# IP5306_IP51081.net
KiCad netlist of a schematic drawn in Altium Designer
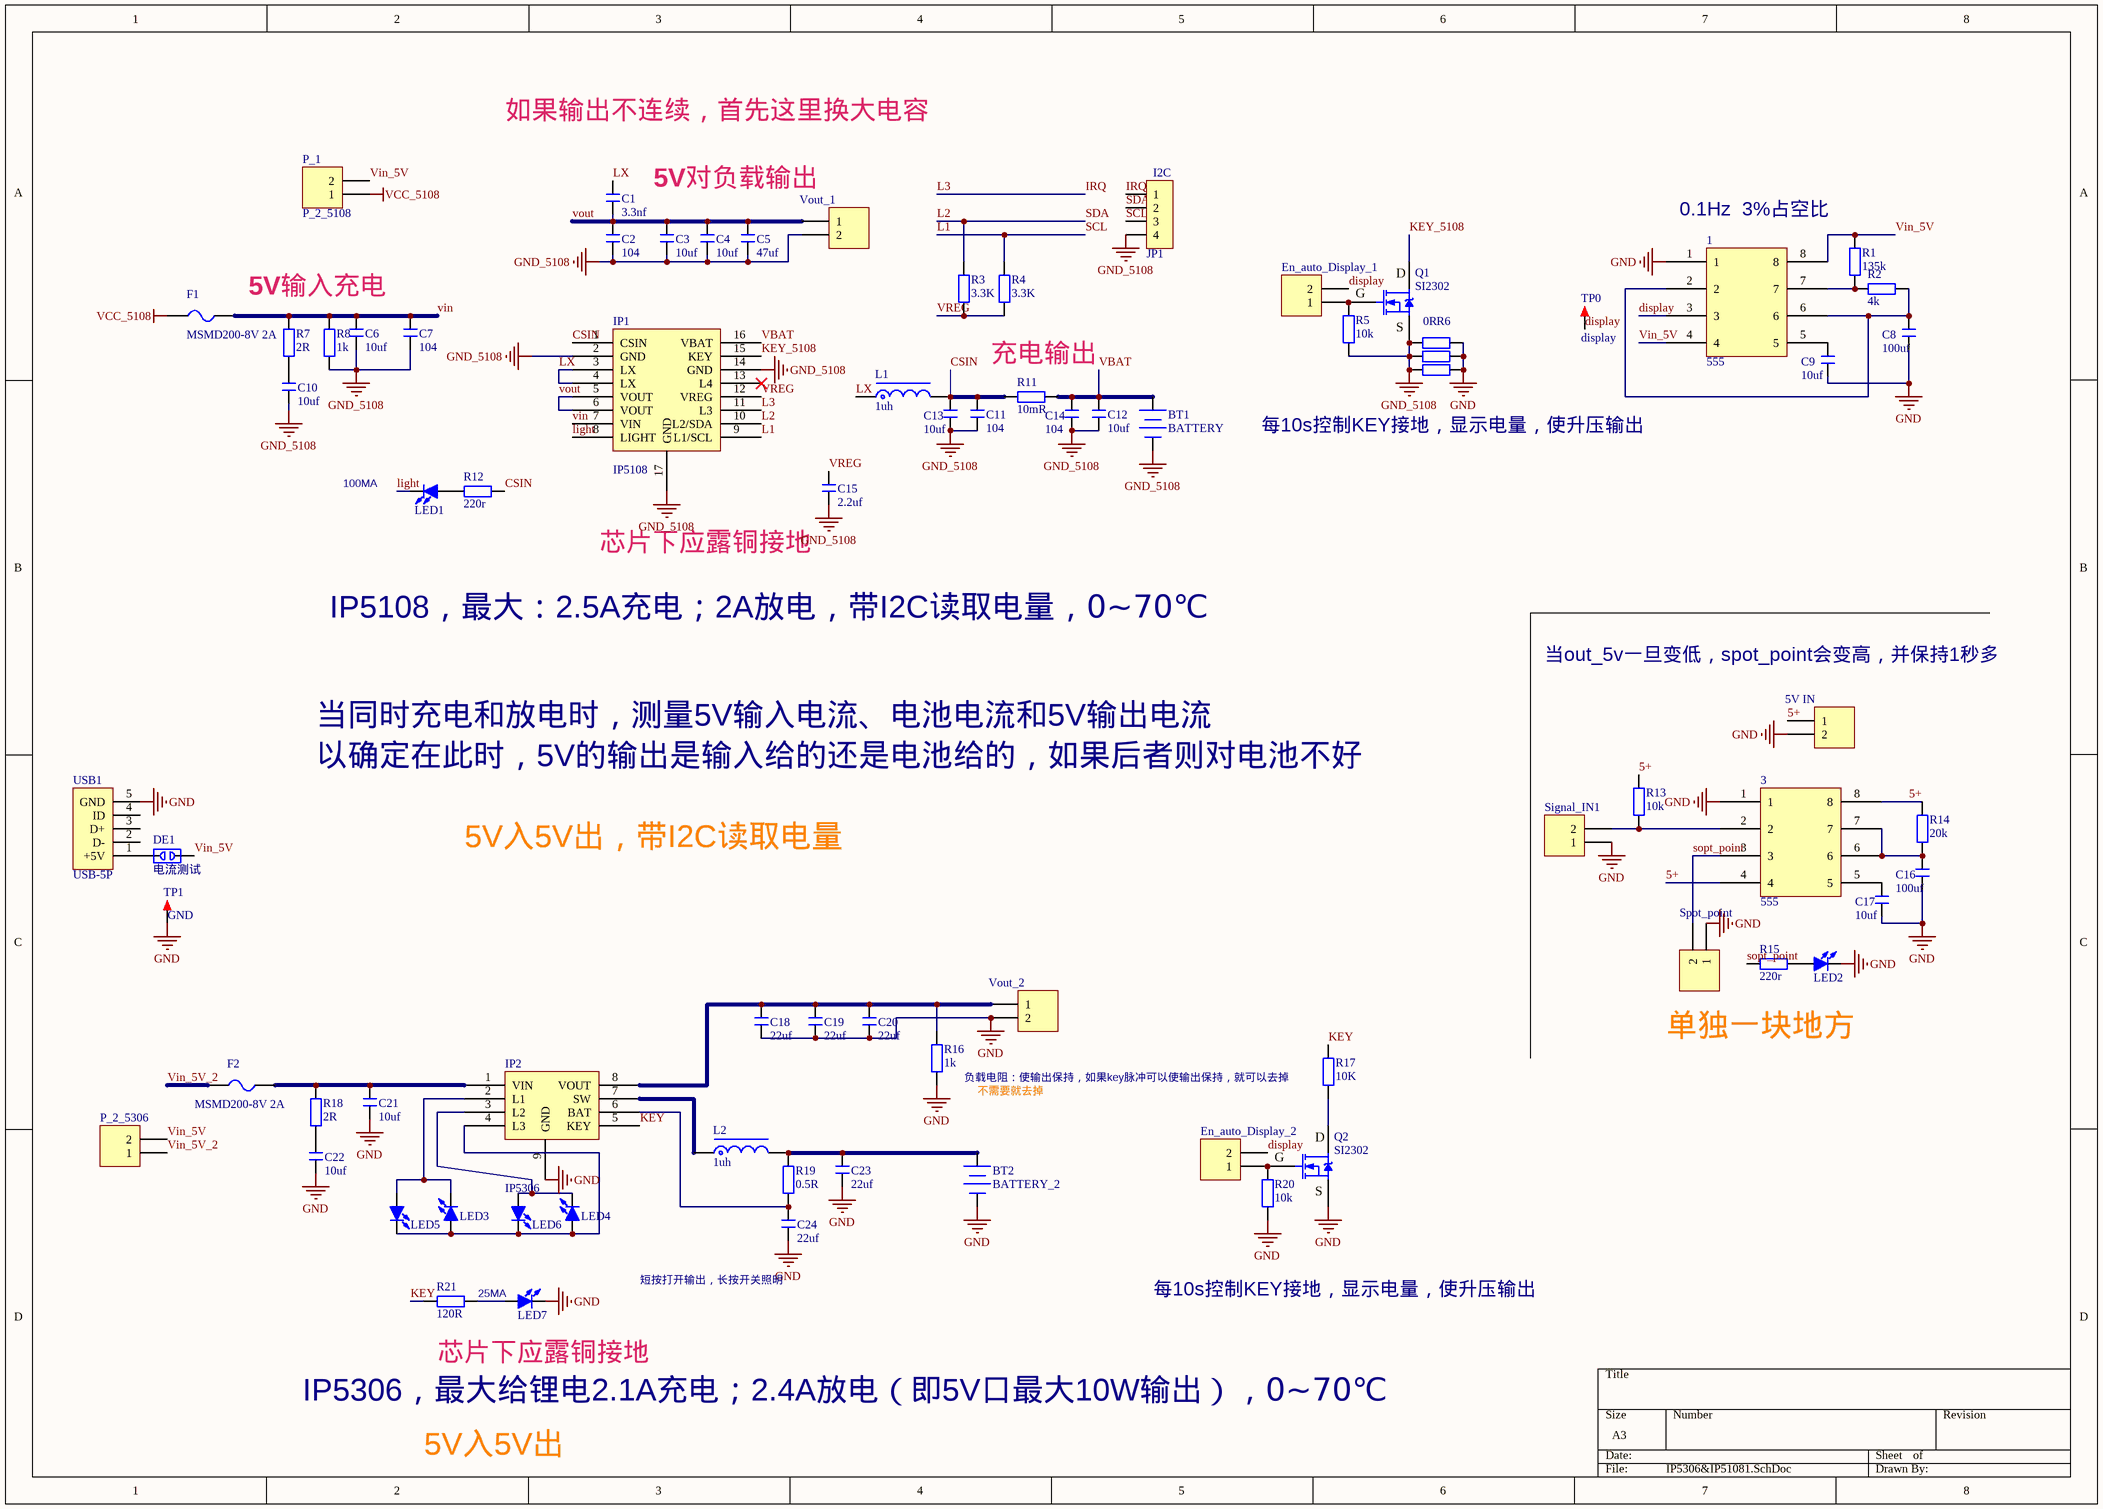
[diagram p0: IP5306&IP51081.SchDoc]

(export (version "E")
  (design (tool "Eeschema 10.0.6"))
  (components
    (comp (ref "1") (value "555") (footprint "SOP8_N") (libsource (lib "集成块") (part "555")))
    (comp (ref "2")
      (value "5V IN")
      (footprint "HDR1X2")
      (description "Header, 2-Pin")
      (fields (field (name "PUBLISHER") "Altium Limited"))
      (libsource (lib "") (part "Header 2_1"))
    )
    (comp (ref "3") (value "555") (footprint "SOP8_N") (libsource (lib "集成块") (part "555")))
    (comp (ref "BT1")
      (value "BATTERY")
      (footprint "BAT-2")
      (description "Multicell Battery")
      (fields (field (name "PUBLISHER") "Altium Limited"))
      (libsource (lib "rest") (part "BATTERY"))
    )
    (comp (ref "BT2")
      (value "BATTERY_2")
      (footprint "BAT-2")
      (description "Multicell Battery")
      (fields (field (name "PUBLISHER") "Altium Limited"))
      (libsource (lib "rest") (part "BATTERY"))
    )
    (comp (ref "C1")
      (value "3.3nf")
      (footprint "C 0805_M")
      (description "无极性贴片电容")
      (libsource (lib "3.1   - 电阻-电容-电感") (part "C"))
    )
    (comp (ref "C2")
      (value "104")
      (footprint "C 0805_M")
      (description "无极性贴片电容")
      (libsource (lib "3.1   - 电阻-电容-电感") (part "C"))
    )
    (comp (ref "C3")
      (value "10uf")
      (footprint "C 0805_M")
      (description "无极性贴片电容")
      (libsource (lib "3.1   - 电阻-电容-电感") (part "C"))
    )
    (comp (ref "C4")
      (value "10uf")
      (footprint "C 0805_M")
      (description "无极性贴片电容")
      (libsource (lib "3.1   - 电阻-电容-电感") (part "C"))
    )
    (comp (ref "C5")
      (value "47uf")
      (footprint "CD A(3216)")
      (description "无极性贴片电容")
      (libsource (lib "3.1   - 电阻-电容-电感") (part "C"))
    )
    (comp (ref "C6")
      (value "10uf")
      (footprint "C 0805_M")
      (description "无极性贴片电容")
      (libsource (lib "3.1   - 电阻-电容-电感") (part "C"))
    )
    (comp (ref "C7")
      (value "104")
      (footprint "C 0805_M")
      (description "无极性贴片电容")
      (libsource (lib "3.1   - 电阻-电容-电感") (part "C"))
    )
    (comp (ref "C8")
      (value "100uf")
      (footprint "CD B(3528)")
      (description "无极性贴片电容")
      (libsource (lib "3.1   - 电阻-电容-电感") (part "C"))
    )
    (comp (ref "C9")
      (value "10uf")
      (footprint "C 0805_M")
      (description "无极性贴片电容")
      (libsource (lib "3.1   - 电阻-电容-电感") (part "C"))
    )
    (comp (ref "C10")
      (value "10uf")
      (footprint "C 0805_M")
      (description "无极性贴片电容")
      (libsource (lib "3.1   - 电阻-电容-电感") (part "C"))
    )
    (comp (ref "C11")
      (value "104")
      (footprint "C 0805_M")
      (description "无极性贴片电容")
      (libsource (lib "3.1   - 电阻-电容-电感") (part "C"))
    )
    (comp (ref "C12")
      (value "10uf")
      (footprint "C 0805_M")
      (description "无极性贴片电容")
      (libsource (lib "3.1   - 电阻-电容-电感") (part "C"))
    )
    (comp (ref "C13")
      (value "10uf")
      (footprint "C 0805_M")
      (description "无极性贴片电容")
      (libsource (lib "3.1   - 电阻-电容-电感") (part "C"))
    )
    (comp (ref "C14")
      (value "104")
      (footprint "C 0805_M")
      (description "无极性贴片电容")
      (libsource (lib "3.1   - 电阻-电容-电感") (part "C"))
    )
    (comp (ref "C15")
      (value "2.2uf")
      (footprint "C 0805_M")
      (description "无极性贴片电容")
      (libsource (lib "3.1   - 电阻-电容-电感") (part "C"))
    )
    (comp (ref "C16")
      (value "100uf")
      (footprint "CD B(3528)")
      (description "无极性贴片电容")
      (libsource (lib "3.1   - 电阻-电容-电感") (part "C"))
    )
    (comp (ref "C17")
      (value "10uf")
      (footprint "C 0805_M")
      (description "无极性贴片电容")
      (libsource (lib "3.1   - 电阻-电容-电感") (part "C"))
    )
    (comp (ref "C18")
      (value "22uf")
      (footprint "C 0805_M")
      (description "无极性贴片电容")
      (libsource (lib "3.1   - 电阻-电容-电感") (part "C"))
    )
    (comp (ref "C19")
      (value "22uf")
      (footprint "C 0805_M")
      (description "无极性贴片电容")
      (libsource (lib "3.1   - 电阻-电容-电感") (part "C"))
    )
    (comp (ref "C20")
      (value "22uf")
      (footprint "C 0805_M")
      (description "无极性贴片电容")
      (libsource (lib "3.1   - 电阻-电容-电感") (part "C"))
    )
    (comp (ref "C21")
      (value "10uf")
      (footprint "C 0805_M")
      (description "无极性贴片电容")
      (libsource (lib "3.1   - 电阻-电容-电感") (part "C"))
    )
    (comp (ref "C22")
      (value "10uf")
      (footprint "C 0805_M")
      (description "无极性贴片电容")
      (libsource (lib "3.1   - 电阻-电容-电感") (part "C"))
    )
    (comp (ref "C23")
      (value "22uf")
      (footprint "C 0805_M")
      (description "无极性贴片电容")
      (libsource (lib "3.1   - 电阻-电容-电感") (part "C"))
    )
    (comp (ref "C24")
      (value "22uf")
      (footprint "C 0805_M")
      (description "无极性贴片电容")
      (libsource (lib "3.1   - 电阻-电容-电感") (part "C"))
    )
    (comp (ref "DE1")
      (value "电流测试")
      (footprint "DEBUG_B")
      (description "调试断点焊盘")
      (libsource (lib "15.1 - 未分类器件") (part "DEBUG"))
    )
    (comp (ref "En_auto_Display_1")
      (value "En_auto_Display_1")
      (footprint "HDR1X2")
      (description "Header, 2-Pin")
      (fields (field (name "PUBLISHER") "Altium Limited"))
      (libsource (lib "Miscellaneous Connectors") (part "Header 2"))
    )
    (comp (ref "En_auto_Display_2")
      (value "En_auto_Display_2")
      (footprint "HDR1X2")
      (description "Header, 2-Pin")
      (fields (field (name "PUBLISHER") "Altium Limited"))
      (libsource (lib "Miscellaneous Connectors") (part "Header 2"))
    )
    (comp (ref "F1")
      (value "MSMD200-8V 2A")
      (footprint "FU 1812")
      (description "贴片保险丝")
      (libsource (lib "10.1 - 保险丝-晶振") (part "FU"))
    )
    (comp (ref "F2")
      (value "MSMD200-8V 2A")
      (footprint "FU 1812")
      (description "贴片保险丝")
      (libsource (lib "10.1 - 保险丝-晶振") (part "FU"))
    )
    (comp (ref "IP1") (value "IP5108") (footprint "ESOP16_M") (libsource (lib "电源管理") (part "IP5108")))
    (comp (ref "IP2") (value "IP5306") (footprint "ESOP8_M") (libsource (lib "电源管理") (part "IP5306")))
    (comp (ref "JP1")
      (value "I2C")
      (footprint "HDR2.54-LI-4P")
      (description "4P接插件")
      (libsource (lib "4.5   - 接插件-脚距2.54") (part "Header 4"))
    )
    (comp (ref "L1")
      (value "1uh")
      (footprint "L-SMD-0630")
      (description "功率屏蔽电感")
      (libsource (lib "3.1   - 电阻-电容-电感") (part "L-CDRH"))
    )
    (comp (ref "L2")
      (value "1uh")
      (footprint "L-SMD-0630")
      (description "功率屏蔽电感")
      (libsource (lib "3.1   - 电阻-电容-电感") (part "L-CDRH"))
    )
    (comp (ref "LED1")
      (value "light")
      (footprint "LED 0805G")
      (description "贴片LED")
      (libsource (lib "9.1   - LED") (part "LED-SMD"))
    )
    (comp (ref "LED2")
      (value "led")
      (footprint "LED 0805G")
      (description "贴片LED")
      (libsource (lib "9.1   - LED") (part "LED-SMD"))
    )
    (comp (ref "LED3")
      (value "led2")
      (footprint "LED 0805G")
      (description "贴片LED")
      (libsource (lib "9.1   - LED") (part "LED-SMD"))
    )
    (comp (ref "LED4")
      (value "led4")
      (footprint "LED 0805G")
      (description "贴片LED")
      (libsource (lib "9.1   - LED") (part "LED-SMD"))
    )
    (comp (ref "LED5")
      (value "led1")
      (footprint "LED 0805G")
      (description "贴片LED")
      (libsource (lib "9.1   - LED") (part "LED-SMD"))
    )
    (comp (ref "LED6")
      (value "led3")
      (footprint "LED 0805G")
      (description "贴片LED")
      (libsource (lib "9.1   - LED") (part "LED-SMD"))
    )
    (comp (ref "LED7")
      (value "light")
      (footprint "LED 0805G")
      (description "贴片LED")
      (libsource (lib "9.1   - LED") (part "LED-SMD"))
    )
    (comp (ref "P_1")
      (value "P_2_5108")
      (footprint "HDR1X2")
      (description "Header, 2-Pin")
      (fields (field (name "PUBLISHER") "Altium Limited"))
      (libsource (lib "Miscellaneous Connectors") (part "Header 2"))
    )
    (comp (ref "P_2")
      (value "P_2_5306")
      (footprint "HDR1X2")
      (description "Header, 2-Pin")
      (fields (field (name "PUBLISHER") "Altium Limited"))
      (libsource (lib "Miscellaneous Connectors") (part "Header 2"))
    )
    (comp (ref "Q1")
      (value "SI2302")
      (footprint "SOT23-3N")
      (description "N沟道场效应管")
      (libsource (lib "6.1   - 场效应管-可控硅") (part "SI2302"))
    )
    (comp (ref "Q2")
      (value "SI2302")
      (footprint "SOT23-3N")
      (description "N沟道场效应管")
      (libsource (lib "6.1   - 场效应管-可控硅") (part "SI2302"))
    )
    (comp (ref "R1")
      (value "135k")
      (footprint "R 0805_M")
      (description "贴片电阻")
      (libsource (lib "3.1   - 电阻-电容-电感") (part "R"))
    )
    (comp (ref "R2")
      (value "4k")
      (footprint "R 0805_M")
      (description "贴片电阻")
      (libsource (lib "3.1   - 电阻-电容-电感") (part "R"))
    )
    (comp (ref "R3")
      (value "3.3K")
      (footprint "R 0805_M")
      (description "贴片电阻")
      (libsource (lib "3.1   - 电阻-电容-电感") (part "R"))
    )
    (comp (ref "R4")
      (value "3.3K")
      (footprint "R 0805_M")
      (description "贴片电阻")
      (libsource (lib "3.1   - 电阻-电容-电感") (part "R"))
    )
    (comp (ref "R5")
      (value "10k")
      (footprint "R 0805_M")
      (description "贴片电阻")
      (libsource (lib "3.1   - 电阻-电容-电感") (part "R"))
    )
    (comp (ref "R6")
      (value "0R")
      (footprint "R 0805_M")
      (description "贴片电阻")
      (libsource (lib "3.1   - 电阻-电容-电感") (part "R"))
    )
    (comp (ref "R7")
      (value "2R")
      (footprint "R 0805_M")
      (description "贴片电阻")
      (libsource (lib "3.1   - 电阻-电容-电感") (part "R"))
    )
    (comp (ref "R8")
      (value "1k")
      (footprint "R 0805_M")
      (description "贴片电阻")
      (libsource (lib "3.1   - 电阻-电容-电感") (part "R"))
    )
    (comp (ref "R9")
      (value "0R")
      (footprint "R 0805_M")
      (description "贴片电阻")
      (libsource (lib "3.1   - 电阻-电容-电感") (part "R"))
    )
    (comp (ref "R10")
      (value "0R")
      (footprint "R 0805_M")
      (description "贴片电阻")
      (libsource (lib "3.1   - 电阻-电容-电感") (part "R"))
    )
    (comp (ref "R11")
      (value "10mR")
      (footprint "R 2512-HP_L")
      (description "贴片电阻")
      (libsource (lib "3.1   - 电阻-电容-电感") (part "R"))
    )
    (comp (ref "R12")
      (value "220r")
      (footprint "R 0805_M")
      (description "贴片电阻")
      (libsource (lib "3.1   - 电阻-电容-电感") (part "R"))
    )
    (comp (ref "R13")
      (value "10k")
      (footprint "R 0805_M")
      (description "贴片电阻")
      (libsource (lib "3.1   - 电阻-电容-电感") (part "R"))
    )
    (comp (ref "R14")
      (value "20k")
      (footprint "R 0805_M")
      (description "贴片电阻")
      (libsource (lib "3.1   - 电阻-电容-电感") (part "R"))
    )
    (comp (ref "R15")
      (value "220r")
      (footprint "R 0805_M")
      (description "贴片电阻")
      (libsource (lib "3.1   - 电阻-电容-电感") (part "R"))
    )
    (comp (ref "R16")
      (value "1k")
      (footprint "R 0805_M")
      (description "贴片电阻")
      (libsource (lib "3.1   - 电阻-电容-电感") (part "R"))
    )
    (comp (ref "R17")
      (value "10K")
      (footprint "R 0805_M")
      (description "贴片电阻")
      (libsource (lib "3.1   - 电阻-电容-电感") (part "R"))
    )
    (comp (ref "R18")
      (value "2R")
      (footprint "R 0805_M")
      (description "贴片电阻")
      (libsource (lib "3.1   - 电阻-电容-电感") (part "R"))
    )
    (comp (ref "R19")
      (value "0.5R")
      (footprint "R 0805_M")
      (description "贴片电阻")
      (libsource (lib "3.1   - 电阻-电容-电感") (part "R"))
    )
    (comp (ref "R20")
      (value "10k")
      (footprint "R 0805_M")
      (description "贴片电阻")
      (libsource (lib "3.1   - 电阻-电容-电感") (part "R"))
    )
    (comp (ref "R21")
      (value "120R")
      (footprint "R 0805_M")
      (description "贴片电阻")
      (libsource (lib "3.1   - 电阻-电容-电感") (part "R"))
    )
    (comp (ref "Signal_IN1")
      (value "Signal_IN1")
      (footprint "HDR1X2")
      (description "Header, 2-Pin")
      (fields (field (name "PUBLISHER") "Altium Limited"))
      (libsource (lib "Miscellaneous Connectors") (part "Header 2"))
    )
    (comp (ref "Spot_point1")
      (value "Spot_point")
      (footprint "HDR1X2")
      (description "Header, 2-Pin")
      (fields (field (name "PUBLISHER") "Altium Limited"))
      (libsource (lib "") (part "Header 2_2"))
    )
    (comp (ref "TP0")
      (value "display")
      (footprint "TEST 1")
      (description "测试点")
      (libsource (lib "15.1 - 未分类器件") (part "TEST"))
    )
    (comp (ref "TP1")
      (value "GND")
      (footprint "TEST 1")
      (description "测试点")
      (libsource (lib "15.1 - 未分类器件") (part "TEST"))
    )
    (comp (ref "USB1")
      (value "USB-5P")
      (footprint "USB-MICRO_E")
      (description "微型USB母座")
      (libsource (lib "4.1   - 接口类") (part "USB-5P"))
    )
    (comp (ref "Vout_1")
      (value "Vout_1")
      (footprint "HDR1X2")
      (description "Header, 2-Pin")
      (fields (field (name "PUBLISHER") "Altium Limited"))
      (libsource (lib "") (part "Header 2_1"))
    )
    (comp (ref "Vout_2")
      (value "Vout_2")
      (footprint "HDR1X2")
      (description "Header, 2-Pin")
      (fields (field (name "PUBLISHER") "Altium Limited"))
      (libsource (lib "") (part "Header 2_1"))
    )
  )
  (nets
    (net (code "1") (name "/5+") (class "Default")
      (node (ref "2") (pin "1") (pinfunction "1_1") (pintype "passive"))
      (node (ref "3") (pin "4") (pinfunction "4_4") (pintype "passive"))
      (node (ref "3") (pin "8") (pinfunction "8_8") (pintype "passive"))
      (node (ref "R13") (pin "1") (pinfunction "1_1") (pintype "passive"))
      (node (ref "R14") (pin "1") (pinfunction "1_1") (pintype "passive"))
    )
    (net (code "2") (name "/CSIN") (class "Default")
      (node (ref "C11") (pin "2") (pinfunction "2_2") (pintype "passive"))
      (node (ref "C13") (pin "2") (pinfunction "2_2") (pintype "passive"))
      (node (ref "IP1") (pin "1") (pinfunction "CSIN_1") (pintype "passive"))
      (node (ref "L1") (pin "2") (pinfunction "2_2") (pintype "passive"))
      (node (ref "R11") (pin "1") (pinfunction "1_1") (pintype "passive"))
      (node (ref "R12") (pin "2") (pinfunction "2_2") (pintype "passive"))
    )
    (net (code "3") (name "/IRQ") (class "Default")
      (node (ref "IP1") (pin "11") (pinfunction "L3_11") (pintype "passive"))
      (node (ref "JP1") (pin "1") (pinfunction "1_1") (pintype "passive"))
    )
    (net (code "4") (name "/KEY") (class "Default")
      (node (ref "IP2") (pin "5") (pinfunction "KEY_5") (pintype "passive"))
      (node (ref "R17") (pin "1") (pinfunction "1_1") (pintype "passive"))
      (node (ref "R21") (pin "1") (pinfunction "1_1") (pintype "passive"))
    )
    (net (code "5") (name "/KEY_5108") (class "Default")
      (node (ref "IP1") (pin "15") (pinfunction "KEY_15") (pintype "passive"))
      (node (ref "Q1") (pin "3") (pinfunction "D_3") (pintype "passive"))
    )
    (net (code "6") (name "/L1") (class "Default")
      (node (ref "IP1") (pin "9") (pinfunction "L1/SCL_9") (pintype "passive"))
      (node (ref "JP1") (pin "3") (pinfunction "3_3") (pintype "passive"))
      (node (ref "R4") (pin "1") (pinfunction "1_1") (pintype "passive"))
    )
    (net (code "7") (name "/L2") (class "Default")
      (node (ref "IP1") (pin "10") (pinfunction "L2/SDA_10") (pintype "passive"))
      (node (ref "JP1") (pin "2") (pinfunction "2_2") (pintype "passive"))
      (node (ref "R3") (pin "1") (pinfunction "1_1") (pintype "passive"))
    )
    (net (code "8") (name "/LX") (class "Default")
      (node (ref "C1") (pin "2") (pinfunction "2_2") (pintype "passive"))
      (node (ref "IP1") (pin "3") (pinfunction "LX_3") (pintype "passive"))
      (node (ref "IP1") (pin "4") (pinfunction "LX_4") (pintype "passive"))
      (node (ref "L1") (pin "1") (pinfunction "1_1") (pintype "passive"))
    )
    (net (code "9") (name "/VBAT") (class "Default")
      (node (ref "BT1") (pin "1") (pinfunction "+_1") (pintype "passive"))
      (node (ref "C12") (pin "2") (pinfunction "2_2") (pintype "passive"))
      (node (ref "C14") (pin "2") (pinfunction "2_2") (pintype "passive"))
      (node (ref "IP1") (pin "16") (pinfunction "VBAT_16") (pintype "passive"))
      (node (ref "R11") (pin "2") (pinfunction "2_2") (pintype "passive"))
    )
    (net (code "10") (name "/VREG") (class "Default")
      (node (ref "C15") (pin "2") (pinfunction "2_2") (pintype "passive"))
      (node (ref "IP1") (pin "12") (pinfunction "VREG_12") (pintype "passive"))
      (node (ref "R3") (pin "2") (pinfunction "2_2") (pintype "passive"))
      (node (ref "R4") (pin "2") (pinfunction "2_2") (pintype "passive"))
    )
    (net (code "11") (name "/Vin_5V") (class "Default")
      (node (ref "1") (pin "4") (pinfunction "4_4") (pintype "passive"))
      (node (ref "1") (pin "8") (pinfunction "8_8") (pintype "passive"))
      (node (ref "DE1") (pin "2") (pinfunction "2_2") (pintype "passive"))
      (node (ref "P_1") (pin "2") (pinfunction "2_2") (pintype "passive"))
      (node (ref "P_2") (pin "2") (pinfunction "2_2") (pintype "passive"))
      (node (ref "R1") (pin "2") (pinfunction "2_2") (pintype "passive"))
    )
    (net (code "12") (name "/Vin_5V_2") (class "Default")
      (node (ref "F2") (pin "1") (pinfunction "1_1") (pintype "passive"))
      (node (ref "P_2") (pin "1") (pinfunction "1_1") (pintype "passive"))
    )
    (net (code "13") (name "/display") (class "Default")
      (node (ref "1") (pin "3") (pinfunction "3_3") (pintype "passive"))
      (node (ref "En_auto_Display_1") (pin "2") (pinfunction "2_2") (pintype "passive"))
      (node (ref "En_auto_Display_2") (pin "2") (pinfunction "2_2") (pintype "passive"))
      (node (ref "TP0") (pin "1") (pinfunction "1_1") (pintype "passive"))
    )
    (net (code "14") (name "/light") (class "Default")
      (node (ref "IP1") (pin "8") (pinfunction "LIGHT_8") (pintype "passive"))
      (node (ref "LED1") (pin "2") (pinfunction "K_2") (pintype "passive"))
    )
    (net (code "15") (name "/sopt_point") (class "Default")
      (node (ref "3") (pin "3") (pinfunction "3_3") (pintype "passive"))
      (node (ref "R15") (pin "2") (pinfunction "2_2") (pintype "passive"))
      (node (ref "Spot_point1") (pin "2") (pinfunction "2_2") (pintype "passive"))
    )
    (net (code "16") (name "/vin") (class "Default")
      (node (ref "C6") (pin "2") (pinfunction "2_2") (pintype "passive"))
      (node (ref "C7") (pin "2") (pinfunction "2_2") (pintype "passive"))
      (node (ref "F1") (pin "2") (pinfunction "2_2") (pintype "passive"))
      (node (ref "IP1") (pin "7") (pinfunction "VIN_7") (pintype "passive"))
      (node (ref "R7") (pin "1") (pinfunction "1_1") (pintype "passive"))
      (node (ref "R8") (pin "1") (pinfunction "1_1") (pintype "passive"))
    )
    (net (code "17") (name "/vout") (class "Default")
      (node (ref "C1") (pin "1") (pinfunction "1_1") (pintype "passive"))
      (node (ref "C2") (pin "2") (pinfunction "2_2") (pintype "passive"))
      (node (ref "C3") (pin "2") (pinfunction "2_2") (pintype "passive"))
      (node (ref "C4") (pin "2") (pinfunction "2_2") (pintype "passive"))
      (node (ref "C5") (pin "2") (pinfunction "2_2") (pintype "passive"))
      (node (ref "IP1") (pin "5") (pinfunction "VOUT_5") (pintype "passive"))
      (node (ref "IP1") (pin "6") (pinfunction "VOUT_6") (pintype "passive"))
      (node (ref "Vout_1") (pin "1") (pinfunction "1_1") (pintype "passive"))
    )
    (net (code "18") (name "GND") (class "Default")
      (node (ref "1") (pin "1") (pinfunction "1_1") (pintype "passive"))
      (node (ref "2") (pin "2") (pinfunction "2_2") (pintype "passive"))
      (node (ref "3") (pin "1") (pinfunction "1_1") (pintype "passive"))
      (node (ref "BT2") (pin "2") (pinfunction "-_2") (pintype "passive"))
      (node (ref "C16") (pin "1") (pinfunction "1_1") (pintype "passive"))
      (node (ref "C17") (pin "1") (pinfunction "1_1") (pintype "passive"))
      (node (ref "C18") (pin "1") (pinfunction "1_1") (pintype "passive"))
      (node (ref "C19") (pin "1") (pinfunction "1_1") (pintype "passive"))
      (node (ref "C20") (pin "1") (pinfunction "1_1") (pintype "passive"))
      (node (ref "C21") (pin "1") (pinfunction "1_1") (pintype "passive"))
      (node (ref "C22") (pin "1") (pinfunction "1_1") (pintype "passive"))
      (node (ref "C23") (pin "1") (pinfunction "1_1") (pintype "passive"))
      (node (ref "C24") (pin "1") (pinfunction "1_1") (pintype "passive"))
      (node (ref "C8") (pin "1") (pinfunction "1_1") (pintype "passive"))
      (node (ref "C9") (pin "1") (pinfunction "1_1") (pintype "passive"))
      (node (ref "IP2") (pin "9") (pinfunction "GND_9") (pintype "passive"))
      (node (ref "LED2") (pin "2") (pinfunction "K_2") (pintype "passive"))
      (node (ref "LED7") (pin "2") (pinfunction "K_2") (pintype "passive"))
      (node (ref "Q2") (pin "2") (pinfunction "S_2") (pintype "passive"))
      (node (ref "R10") (pin "2") (pinfunction "2_2") (pintype "passive"))
      (node (ref "R16") (pin "2") (pinfunction "2_2") (pintype "passive"))
      (node (ref "R20") (pin "2") (pinfunction "2_2") (pintype "passive"))
      (node (ref "R6") (pin "2") (pinfunction "2_2") (pintype "passive"))
      (node (ref "R9") (pin "2") (pinfunction "2_2") (pintype "passive"))
      (node (ref "Signal_IN1") (pin "1") (pinfunction "1_1") (pintype "passive"))
      (node (ref "Spot_point1") (pin "1") (pinfunction "1_1") (pintype "passive"))
      (node (ref "TP1") (pin "1") (pinfunction "1_1") (pintype "passive"))
      (node (ref "USB1") (pin "5") (pinfunction "GND_5") (pintype "passive"))
      (node (ref "Vout_2") (pin "2") (pinfunction "2_2") (pintype "passive"))
    )
    (net (code "19") (name "GND_5108") (class "Default")
      (node (ref "BT1") (pin "2") (pinfunction "-_2") (pintype "passive"))
      (node (ref "C10") (pin "1") (pinfunction "1_1") (pintype "passive"))
      (node (ref "C11") (pin "1") (pinfunction "1_1") (pintype "passive"))
      (node (ref "C12") (pin "1") (pinfunction "1_1") (pintype "passive"))
      (node (ref "C13") (pin "1") (pinfunction "1_1") (pintype "passive"))
      (node (ref "C14") (pin "1") (pinfunction "1_1") (pintype "passive"))
      (node (ref "C15") (pin "1") (pinfunction "1_1") (pintype "passive"))
      (node (ref "C2") (pin "1") (pinfunction "1_1") (pintype "passive"))
      (node (ref "C3") (pin "1") (pinfunction "1_1") (pintype "passive"))
      (node (ref "C4") (pin "1") (pinfunction "1_1") (pintype "passive"))
      (node (ref "C5") (pin "1") (pinfunction "1_1") (pintype "passive"))
      (node (ref "C6") (pin "1") (pinfunction "1_1") (pintype "passive"))
      (node (ref "C7") (pin "1") (pinfunction "1_1") (pintype "passive"))
      (node (ref "IP1") (pin "14") (pinfunction "GND_14") (pintype "passive"))
      (node (ref "IP1") (pin "17") (pinfunction "GND_17") (pintype "passive"))
      (node (ref "IP1") (pin "2") (pinfunction "GND_2") (pintype "passive"))
      (node (ref "JP1") (pin "4") (pinfunction "4_4") (pintype "passive"))
      (node (ref "Q1") (pin "2") (pinfunction "S_2") (pintype "passive"))
      (node (ref "R10") (pin "1") (pinfunction "1_1") (pintype "passive"))
      (node (ref "R5") (pin "2") (pinfunction "2_2") (pintype "passive"))
      (node (ref "R6") (pin "1") (pinfunction "1_1") (pintype "passive"))
      (node (ref "R8") (pin "2") (pinfunction "2_2") (pintype "passive"))
      (node (ref "R9") (pin "1") (pinfunction "1_1") (pintype "passive"))
      (node (ref "Vout_1") (pin "2") (pinfunction "2_2") (pintype "passive"))
    )
    (net (code "20") (name "Net-(1-Pad2)") (class "Default")
      (node (ref "1") (pin "2") (pinfunction "2_2") (pintype "passive"))
      (node (ref "1") (pin "6") (pinfunction "6_6") (pintype "passive"))
      (node (ref "C8") (pin "2") (pinfunction "2_2") (pintype "passive"))
      (node (ref "R2") (pin "1") (pinfunction "1_1") (pintype "passive"))
    )
    (net (code "21") (name "Net-(1-Pad5)") (class "Default")
      (node (ref "1") (pin "5") (pinfunction "5_5") (pintype "passive"))
      (node (ref "C9") (pin "2") (pinfunction "2_2") (pintype "passive"))
    )
    (net (code "22") (name "Net-(1-Pad7)") (class "Default")
      (node (ref "1") (pin "7") (pinfunction "7_7") (pintype "passive"))
      (node (ref "R1") (pin "1") (pinfunction "1_1") (pintype "passive"))
      (node (ref "R2") (pin "2") (pinfunction "2_2") (pintype "passive"))
    )
    (net (code "23") (name "Net-(3-Pad2)") (class "Default")
      (node (ref "3") (pin "2") (pinfunction "2_2") (pintype "passive"))
      (node (ref "R13") (pin "2") (pinfunction "2_2") (pintype "passive"))
      (node (ref "Signal_IN1") (pin "2") (pinfunction "2_2") (pintype "passive"))
    )
    (net (code "24") (name "Net-(3-Pad5)") (class "Default")
      (node (ref "3") (pin "5") (pinfunction "5_5") (pintype "passive"))
      (node (ref "C17") (pin "2") (pinfunction "2_2") (pintype "passive"))
    )
    (net (code "25") (name "Net-(3-Pad6)") (class "Default")
      (node (ref "3") (pin "6") (pinfunction "6_6") (pintype "passive"))
      (node (ref "3") (pin "7") (pinfunction "7_7") (pintype "passive"))
      (node (ref "C16") (pin "2") (pinfunction "2_2") (pintype "passive"))
      (node (ref "R14") (pin "2") (pinfunction "2_2") (pintype "passive"))
    )
    (net (code "26") (name "Net-(BT2-+)") (class "Default")
      (node (ref "BT2") (pin "1") (pinfunction "+_1") (pintype "passive"))
      (node (ref "C23") (pin "2") (pinfunction "2_2") (pintype "passive"))
      (node (ref "L2") (pin "2") (pinfunction "2_2") (pintype "passive"))
      (node (ref "R19") (pin "1") (pinfunction "1_1") (pintype "passive"))
    )
    (net (code "27") (name "Net-(C10-Pad2)") (class "Default")
      (node (ref "C10") (pin "2") (pinfunction "2_2") (pintype "passive"))
      (node (ref "R7") (pin "2") (pinfunction "2_2") (pintype "passive"))
    )
    (net (code "28") (name "Net-(C22-Pad2)") (class "Default")
      (node (ref "C22") (pin "2") (pinfunction "2_2") (pintype "passive"))
      (node (ref "R18") (pin "2") (pinfunction "2_2") (pintype "passive"))
    )
    (net (code "29") (name "Net-(IP2-BAT)") (class "Default")
      (node (ref "C24") (pin "2") (pinfunction "2_2") (pintype "passive"))
      (node (ref "IP2") (pin "6") (pinfunction "BAT_6") (pintype "passive"))
      (node (ref "R19") (pin "2") (pinfunction "2_2") (pintype "passive"))
    )
    (net (code "30") (name "Net-(IP2-L1)") (class "Default")
      (node (ref "IP2") (pin "2") (pinfunction "L1_2") (pintype "passive"))
      (node (ref "LED3") (pin "2") (pinfunction "K_2") (pintype "passive"))
      (node (ref "LED5") (pin "1") (pinfunction "A_1") (pintype "passive"))
    )
    (net (code "31") (name "Net-(IP2-L2)") (class "Default")
      (node (ref "IP2") (pin "3") (pinfunction "L2_3") (pintype "passive"))
      (node (ref "LED4") (pin "2") (pinfunction "K_2") (pintype "passive"))
      (node (ref "LED6") (pin "1") (pinfunction "A_1") (pintype "passive"))
    )
    (net (code "32") (name "Net-(IP2-L3)") (class "Default")
      (node (ref "IP2") (pin "4") (pinfunction "L3_4") (pintype "passive"))
      (node (ref "LED3") (pin "1") (pinfunction "A_1") (pintype "passive"))
      (node (ref "LED4") (pin "1") (pinfunction "A_1") (pintype "passive"))
      (node (ref "LED5") (pin "2") (pinfunction "K_2") (pintype "passive"))
      (node (ref "LED6") (pin "2") (pinfunction "K_2") (pintype "passive"))
    )
    (net (code "33") (name "Net-(IP2-SW)") (class "Default")
      (node (ref "IP2") (pin "7") (pinfunction "SW_7") (pintype "passive"))
      (node (ref "L2") (pin "1") (pinfunction "1_1") (pintype "passive"))
    )
    (net (code "34") (name "Net-(IP2-VIN)") (class "Default")
      (node (ref "C21") (pin "2") (pinfunction "2_2") (pintype "passive"))
      (node (ref "F2") (pin "2") (pinfunction "2_2") (pintype "passive"))
      (node (ref "IP2") (pin "1") (pinfunction "VIN_1") (pintype "passive"))
      (node (ref "R18") (pin "1") (pinfunction "1_1") (pintype "passive"))
    )
    (net (code "35") (name "Net-(IP2-VOUT)") (class "Default")
      (node (ref "C18") (pin "2") (pinfunction "2_2") (pintype "passive"))
      (node (ref "C19") (pin "2") (pinfunction "2_2") (pintype "passive"))
      (node (ref "C20") (pin "2") (pinfunction "2_2") (pintype "passive"))
      (node (ref "IP2") (pin "8") (pinfunction "VOUT_8") (pintype "passive"))
      (node (ref "R16") (pin "1") (pinfunction "1_1") (pintype "passive"))
      (node (ref "Vout_2") (pin "1") (pinfunction "1_1") (pintype "passive"))
    )
    (net (code "36") (name "Net-(LED1-A)") (class "Default")
      (node (ref "LED1") (pin "1") (pinfunction "A_1") (pintype "passive"))
      (node (ref "R12") (pin "1") (pinfunction "1_1") (pintype "passive"))
    )
    (net (code "37") (name "Net-(LED2-A)") (class "Default")
      (node (ref "LED2") (pin "1") (pinfunction "A_1") (pintype "passive"))
      (node (ref "R15") (pin "1") (pinfunction "1_1") (pintype "passive"))
    )
    (net (code "38") (name "Net-(LED7-A)") (class "Default")
      (node (ref "LED7") (pin "1") (pinfunction "A_1") (pintype "passive"))
      (node (ref "R21") (pin "2") (pinfunction "2_2") (pintype "passive"))
    )
    (net (code "39") (name "Net-(Q1-G)") (class "Default")
      (node (ref "En_auto_Display_1") (pin "1") (pinfunction "1_1") (pintype "passive"))
      (node (ref "Q1") (pin "1") (pinfunction "G_1") (pintype "passive"))
      (node (ref "R5") (pin "1") (pinfunction "1_1") (pintype "passive"))
    )
    (net (code "40") (name "Net-(Q2-D)") (class "Default")
      (node (ref "Q2") (pin "3") (pinfunction "D_3") (pintype "passive"))
      (node (ref "R17") (pin "2") (pinfunction "2_2") (pintype "passive"))
    )
    (net (code "41") (name "Net-(Q2-G)") (class "Default")
      (node (ref "En_auto_Display_2") (pin "1") (pinfunction "1_1") (pintype "passive"))
      (node (ref "Q2") (pin "1") (pinfunction "G_1") (pintype "passive"))
      (node (ref "R20") (pin "1") (pinfunction "1_1") (pintype "passive"))
    )
    (net (code "42") (name "Net-(USB1-+5V)") (class "Default")
      (node (ref "DE1") (pin "1") (pinfunction "1_1") (pintype "passive"))
      (node (ref "USB1") (pin "1") (pinfunction "+5V_1") (pintype "passive"))
    )
    (net (code "43") (name "VCC_5108") (class "Default")
      (node (ref "F1") (pin "1") (pinfunction "1_1") (pintype "passive"))
      (node (ref "P_1") (pin "1") (pinfunction "1_1") (pintype "passive"))
    )
    (net (code "44") (name "unconnected-(IP1-L4-Pad13)") (class "Default")
      (node (ref "IP1") (pin "13") (pinfunction "L4_13") (pintype "passive+no_connect"))
    )
    (net (code "45") (name "unconnected-(USB1-D+-Pad3)") (class "Default")
      (node (ref "USB1") (pin "3") (pinfunction "D+_3") (pintype "passive"))
    )
    (net (code "46") (name "unconnected-(USB1-D--Pad2)") (class "Default")
      (node (ref "USB1") (pin "2") (pinfunction "D-_2") (pintype "passive"))
    )
    (net (code "47") (name "unconnected-(USB1-ID-Pad4)") (class "Default")
      (node (ref "USB1") (pin "4") (pinfunction "ID_4") (pintype "passive"))
    )
  )
)
